# cyclops.net
KiCad netlist of a schematic drawn in EAGLE
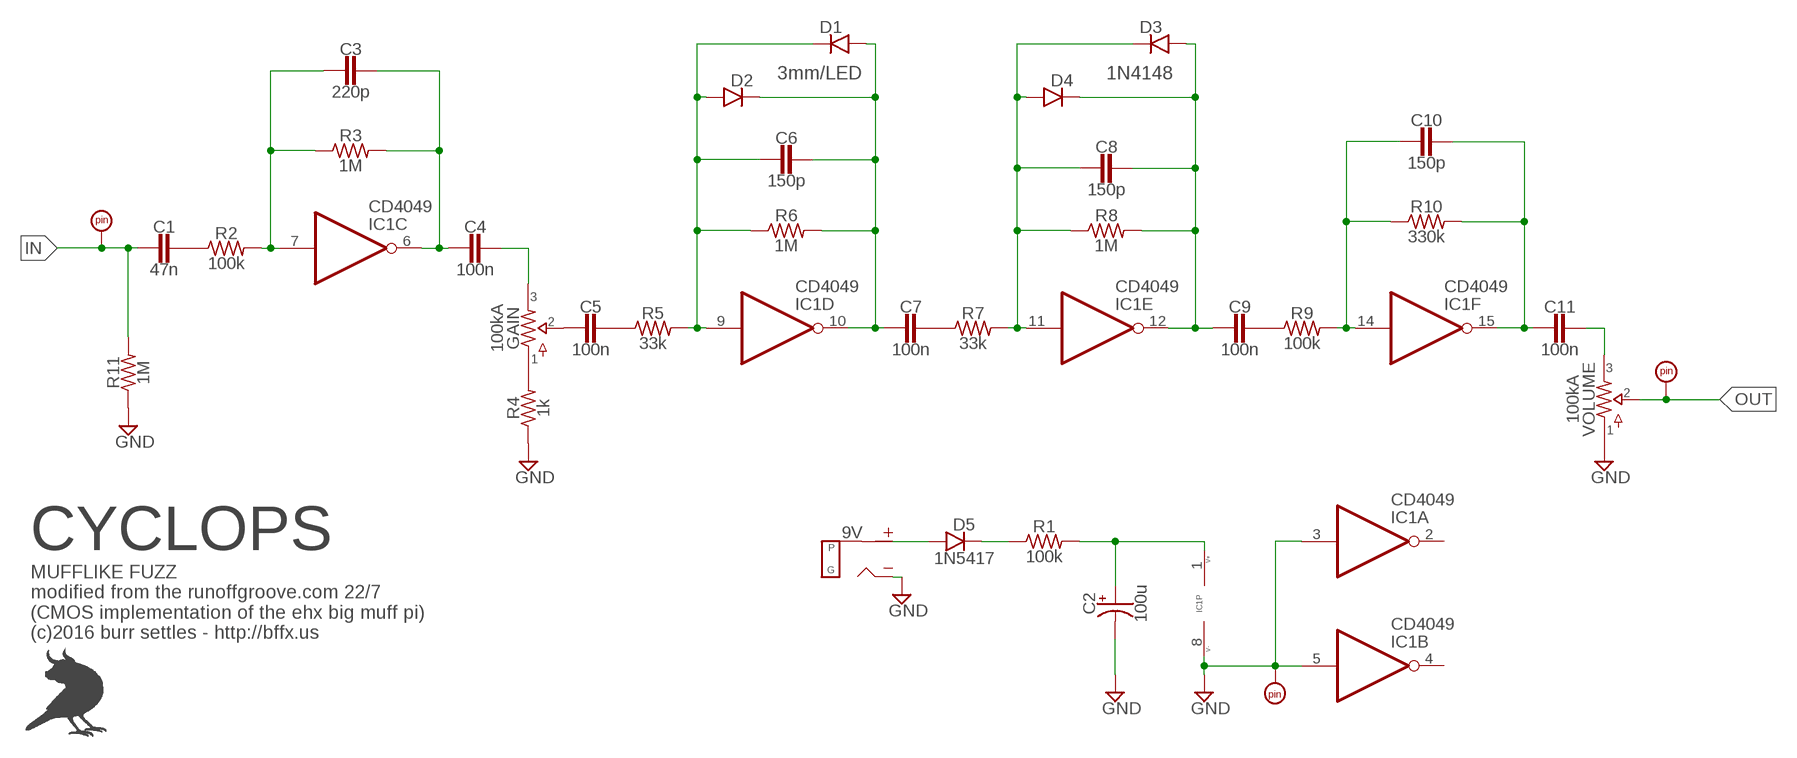
[diagram p0: schematic, sheet 1]

(export (version "E")
  (design (tool "Eeschema 10.0.6"))
  (components
    (comp (ref "9V")
      (value "DC_MONO")
      (footprint "eagle-import:DC")
      (libsource (lib "eagle-import") (part "DC_MONO"))
    )
    (comp (ref "C1")
      (value "47n")
      (footprint "eagle-import:050X030_025_2")
      (libsource (lib "eagle-import") (part "CER/FILM2"))
    )
    (comp (ref "C2")
      (value "100u")
      (footprint "eagle-import:063_025")
      (libsource (lib "eagle-import") (part "0631"))
    )
    (comp (ref "C3")
      (value "220p")
      (footprint "eagle-import:050X030_025_2")
      (libsource (lib "eagle-import") (part "CER/FILM2"))
    )
    (comp (ref "C4")
      (value "100n")
      (footprint "eagle-import:050X030_025_2")
      (libsource (lib "eagle-import") (part "CER/FILM2"))
    )
    (comp (ref "C5")
      (value "100n")
      (footprint "eagle-import:050X030_025_2")
      (libsource (lib "eagle-import") (part "CER/FILM2"))
    )
    (comp (ref "C6")
      (value "150p")
      (footprint "eagle-import:050X030_025_2")
      (libsource (lib "eagle-import") (part "CER/FILM2"))
    )
    (comp (ref "C7")
      (value "100n")
      (footprint "eagle-import:050X030_025_2")
      (libsource (lib "eagle-import") (part "CER/FILM2"))
    )
    (comp (ref "C8")
      (value "150p")
      (footprint "eagle-import:050X030_025_2")
      (libsource (lib "eagle-import") (part "CER/FILM2"))
    )
    (comp (ref "C9")
      (value "100n")
      (footprint "eagle-import:050X030_025_2")
      (libsource (lib "eagle-import") (part "CER/FILM2"))
    )
    (comp (ref "C10")
      (value "150p")
      (footprint "eagle-import:050X030_025_2")
      (libsource (lib "eagle-import") (part "CER/FILM2"))
    )
    (comp (ref "C11")
      (value "100n")
      (footprint "eagle-import:050X030_025_2")
      (libsource (lib "eagle-import") (part "CER/FILM2"))
    )
    (comp (ref "D1")
      (value "DO41.2")
      (footprint "eagle-import:DO41-2")
      (libsource (lib "eagle-import") (part "DO41.2"))
    )
    (comp (ref "D2")
      (value "DO41.2")
      (footprint "eagle-import:DO41-2")
      (libsource (lib "eagle-import") (part "DO41.2"))
    )
    (comp (ref "D3")
      (value "DO41.2")
      (footprint "eagle-import:DO41-2")
      (libsource (lib "eagle-import") (part "DO41.2"))
    )
    (comp (ref "D4")
      (value "DO41.2")
      (footprint "eagle-import:DO41-2")
      (libsource (lib "eagle-import") (part "DO41.2"))
    )
    (comp (ref "D5")
      (value "1N5417")
      (footprint "eagle-import:DO41-3")
      (libsource (lib "eagle-import") (part "DO41.3"))
    )
    (comp (ref "GAIN")
      (value "100kA")
      (footprint "eagle-import:2262_TRIM")
      (libsource (lib "eagle-import") (part "POTSTRIM"))
    )
    (comp (ref "GND")
      (value "PADRND")
      (footprint "eagle-import:ROUND")
      (libsource (lib "eagle-import") (part "PADRND"))
    )
    (comp (ref "IC1")
      (value "CD4049")
      (footprint "eagle-import:DIL16")
      (libsource (lib "eagle-import") (part "CD4049UBE"))
    )
    (comp (ref "IN")
      (value "PADSQR")
      (footprint "eagle-import:SQUARE")
      (libsource (lib "eagle-import") (part "PADSQR"))
    )
    (comp (ref "OUT")
      (value "PADSQR")
      (footprint "eagle-import:SQUARE")
      (libsource (lib "eagle-import") (part "PADSQR"))
    )
    (comp (ref "R1")
      (value "100k")
      (footprint "eagle-import:R0207_2V")
      (libsource (lib "eagle-import") (part "R_.2"))
    )
    (comp (ref "R2")
      (value "100k")
      (footprint "eagle-import:R0207_2V")
      (libsource (lib "eagle-import") (part "R_.2"))
    )
    (comp (ref "R3")
      (value "1M")
      (footprint "eagle-import:R0207_2V")
      (libsource (lib "eagle-import") (part "R_.2"))
    )
    (comp (ref "R4")
      (value "1k")
      (footprint "eagle-import:R0207_2V")
      (libsource (lib "eagle-import") (part "R_.2"))
    )
    (comp (ref "R5")
      (value "33k")
      (footprint "eagle-import:R0207_2V")
      (libsource (lib "eagle-import") (part "R_.2"))
    )
    (comp (ref "R6")
      (value "1M")
      (footprint "eagle-import:R0207_2V")
      (libsource (lib "eagle-import") (part "R_.2"))
    )
    (comp (ref "R7")
      (value "33k")
      (footprint "eagle-import:R0207_2V")
      (libsource (lib "eagle-import") (part "R_.2"))
    )
    (comp (ref "R8")
      (value "1M")
      (footprint "eagle-import:R0207_2V")
      (libsource (lib "eagle-import") (part "R_.2"))
    )
    (comp (ref "R9")
      (value "100k")
      (footprint "eagle-import:R0207_2V")
      (libsource (lib "eagle-import") (part "R_.2"))
    )
    (comp (ref "R10")
      (value "330k")
      (footprint "eagle-import:R0207_2V")
      (libsource (lib "eagle-import") (part "R_.2"))
    )
    (comp (ref "R11")
      (value "1M")
      (footprint "eagle-import:R0207_2V")
      (libsource (lib "eagle-import") (part "R_.2"))
    )
    (comp (ref "VOLUME")
      (value "100kA")
      (footprint "eagle-import:PADS_SMALL")
      (libsource (lib "eagle-import") (part "POTSSMALL_PADS"))
    )
  )
  (nets
    (net (code "1") (name "GND") (class "Default")
      (node (ref "9V") (pin "S") (pinfunction "SLEEVE_S") (pintype "passive"))
      (node (ref "C2") (pin "-") (pinfunction "-_-") (pintype "passive"))
      (node (ref "GND") (pin "1") (pinfunction "P$1_1") (pintype "bidirectional"))
      (node (ref "IC1") (pin "3") (pinfunction "I_3") (pintype "input"))
      (node (ref "IC1") (pin "5") (pinfunction "I_5") (pintype "input"))
      (node (ref "IC1") (pin "8") (pinfunction "VSS_8") (pintype "power_in"))
      (node (ref "R11") (pin "1") (pinfunction "1_1") (pintype "passive"))
      (node (ref "R4") (pin "1") (pinfunction "1_1") (pintype "passive"))
      (node (ref "VOLUME") (pin "1") (pinfunction "1_1") (pintype "passive"))
    )
    (net (code "2") (name "IN") (class "Default")
      (node (ref "C1") (pin "2") (pinfunction "2_2") (pintype "passive"))
      (node (ref "IN") (pin "1") (pinfunction "P$1_1") (pintype "bidirectional"))
      (node (ref "R11") (pin "2") (pinfunction "2_2") (pintype "passive"))
    )
    (net (code "3") (name "Net-(9V-TIP)") (class "Default")
      (node (ref "9V") (pin "T") (pinfunction "TIP_T") (pintype "passive"))
      (node (ref "D5") (pin "A") (pinfunction "A_A") (pintype "passive"))
    )
    (net (code "4") (name "Net-(C1-Pad1)") (class "Default")
      (node (ref "C1") (pin "1") (pinfunction "1_1") (pintype "passive"))
      (node (ref "R2") (pin "1") (pinfunction "1_1") (pintype "passive"))
    )
    (net (code "5") (name "Net-(C4-Pad1)") (class "Default")
      (node (ref "C4") (pin "1") (pinfunction "1_1") (pintype "passive"))
      (node (ref "GAIN") (pin "3") (pinfunction "3_3") (pintype "passive"))
    )
    (net (code "6") (name "Net-(C5-Pad1)") (class "Default")
      (node (ref "C5") (pin "1") (pinfunction "1_1") (pintype "passive"))
      (node (ref "R5") (pin "1") (pinfunction "1_1") (pintype "passive"))
    )
    (net (code "7") (name "Net-(C5-Pad2)") (class "Default")
      (node (ref "C5") (pin "2") (pinfunction "2_2") (pintype "passive"))
      (node (ref "GAIN") (pin "2") (pinfunction "2_2") (pintype "passive"))
    )
    (net (code "8") (name "Net-(C7-Pad1)") (class "Default")
      (node (ref "C7") (pin "1") (pinfunction "1_1") (pintype "passive"))
      (node (ref "R7") (pin "1") (pinfunction "1_1") (pintype "passive"))
    )
    (net (code "9") (name "Net-(C9-Pad1)") (class "Default")
      (node (ref "C9") (pin "1") (pinfunction "1_1") (pintype "passive"))
      (node (ref "R9") (pin "1") (pinfunction "1_1") (pintype "passive"))
    )
    (net (code "10") (name "Net-(C11-Pad1)") (class "Default")
      (node (ref "C11") (pin "1") (pinfunction "1_1") (pintype "passive"))
      (node (ref "VOLUME") (pin "3") (pinfunction "3_3") (pintype "passive"))
    )
    (net (code "11") (name "Net-(D5-PadC)") (class "Default")
      (node (ref "D5") (pin "C") (pinfunction "C_C") (pintype "passive"))
      (node (ref "R1") (pin "1") (pinfunction "1_1") (pintype "passive"))
    )
    (net (code "12") (name "Net-(GAIN-Pad1)") (class "Default")
      (node (ref "GAIN") (pin "1") (pinfunction "1_1") (pintype "passive"))
      (node (ref "R4") (pin "2") (pinfunction "2_2") (pintype "passive"))
    )
    (net (code "13") (name "Net-(IC1C-I)") (class "Default")
      (node (ref "C3") (pin "2") (pinfunction "2_2") (pintype "passive"))
      (node (ref "IC1") (pin "7") (pinfunction "I_7") (pintype "input"))
      (node (ref "R2") (pin "2") (pinfunction "2_2") (pintype "passive"))
      (node (ref "R3") (pin "1") (pinfunction "1_1") (pintype "passive"))
    )
    (net (code "14") (name "Net-(IC1C-O)") (class "Default")
      (node (ref "C3") (pin "1") (pinfunction "1_1") (pintype "passive"))
      (node (ref "C4") (pin "2") (pinfunction "2_2") (pintype "passive"))
      (node (ref "IC1") (pin "6") (pinfunction "O_6") (pintype "output"))
      (node (ref "R3") (pin "2") (pinfunction "2_2") (pintype "passive"))
    )
    (net (code "15") (name "Net-(IC1D-I)") (class "Default")
      (node (ref "C6") (pin "2") (pinfunction "2_2") (pintype "passive"))
      (node (ref "D1") (pin "C") (pinfunction "C_C") (pintype "passive"))
      (node (ref "D2") (pin "A") (pinfunction "A_A") (pintype "passive"))
      (node (ref "IC1") (pin "9") (pinfunction "I_9") (pintype "input"))
      (node (ref "R5") (pin "2") (pinfunction "2_2") (pintype "passive"))
      (node (ref "R6") (pin "1") (pinfunction "1_1") (pintype "passive"))
    )
    (net (code "16") (name "Net-(IC1D-O)") (class "Default")
      (node (ref "C6") (pin "1") (pinfunction "1_1") (pintype "passive"))
      (node (ref "C7") (pin "2") (pinfunction "2_2") (pintype "passive"))
      (node (ref "D1") (pin "A") (pinfunction "A_A") (pintype "passive"))
      (node (ref "D2") (pin "C") (pinfunction "C_C") (pintype "passive"))
      (node (ref "IC1") (pin "10") (pinfunction "O_10") (pintype "output"))
      (node (ref "R6") (pin "2") (pinfunction "2_2") (pintype "passive"))
    )
    (net (code "17") (name "Net-(IC1E-I)") (class "Default")
      (node (ref "C8") (pin "2") (pinfunction "2_2") (pintype "passive"))
      (node (ref "D3") (pin "C") (pinfunction "C_C") (pintype "passive"))
      (node (ref "D4") (pin "A") (pinfunction "A_A") (pintype "passive"))
      (node (ref "IC1") (pin "11") (pinfunction "I_11") (pintype "input"))
      (node (ref "R7") (pin "2") (pinfunction "2_2") (pintype "passive"))
      (node (ref "R8") (pin "1") (pinfunction "1_1") (pintype "passive"))
    )
    (net (code "18") (name "Net-(IC1E-O)") (class "Default")
      (node (ref "C8") (pin "1") (pinfunction "1_1") (pintype "passive"))
      (node (ref "C9") (pin "2") (pinfunction "2_2") (pintype "passive"))
      (node (ref "D3") (pin "A") (pinfunction "A_A") (pintype "passive"))
      (node (ref "D4") (pin "C") (pinfunction "C_C") (pintype "passive"))
      (node (ref "IC1") (pin "12") (pinfunction "O_12") (pintype "output"))
      (node (ref "R8") (pin "2") (pinfunction "2_2") (pintype "passive"))
    )
    (net (code "19") (name "Net-(IC1F-I)") (class "Default")
      (node (ref "C10") (pin "2") (pinfunction "2_2") (pintype "passive"))
      (node (ref "IC1") (pin "14") (pinfunction "I_14") (pintype "input"))
      (node (ref "R10") (pin "1") (pinfunction "1_1") (pintype "passive"))
      (node (ref "R9") (pin "2") (pinfunction "2_2") (pintype "passive"))
    )
    (net (code "20") (name "Net-(IC1F-O)") (class "Default")
      (node (ref "C10") (pin "1") (pinfunction "1_1") (pintype "passive"))
      (node (ref "C11") (pin "2") (pinfunction "2_2") (pintype "passive"))
      (node (ref "IC1") (pin "15") (pinfunction "O_15") (pintype "output"))
      (node (ref "R10") (pin "2") (pinfunction "2_2") (pintype "passive"))
    )
    (net (code "21") (name "Net-(IC1G-VDD)") (class "Default")
      (node (ref "C2") (pin "+") (pinfunction "+_+") (pintype "passive"))
      (node (ref "IC1") (pin "1") (pinfunction "VDD_1") (pintype "power_in"))
      (node (ref "R1") (pin "2") (pinfunction "2_2") (pintype "passive"))
    )
    (net (code "22") (name "OUT") (class "Default")
      (node (ref "OUT") (pin "1") (pinfunction "P$1_1") (pintype "bidirectional"))
      (node (ref "VOLUME") (pin "2") (pinfunction "2_2") (pintype "passive"))
    )
    (net (code "23") (name "unconnected-(IC1A-O-Pad2)") (class "Default")
      (node (ref "IC1") (pin "2") (pinfunction "O_2") (pintype "output"))
    )
    (net (code "24") (name "unconnected-(IC1B-O-Pad4)") (class "Default")
      (node (ref "IC1") (pin "4") (pinfunction "O_4") (pintype "output"))
    )
  )
)
